# sttslife_2022-01-20.net
KiCad netlist of a schematic drawn in Altium Designer
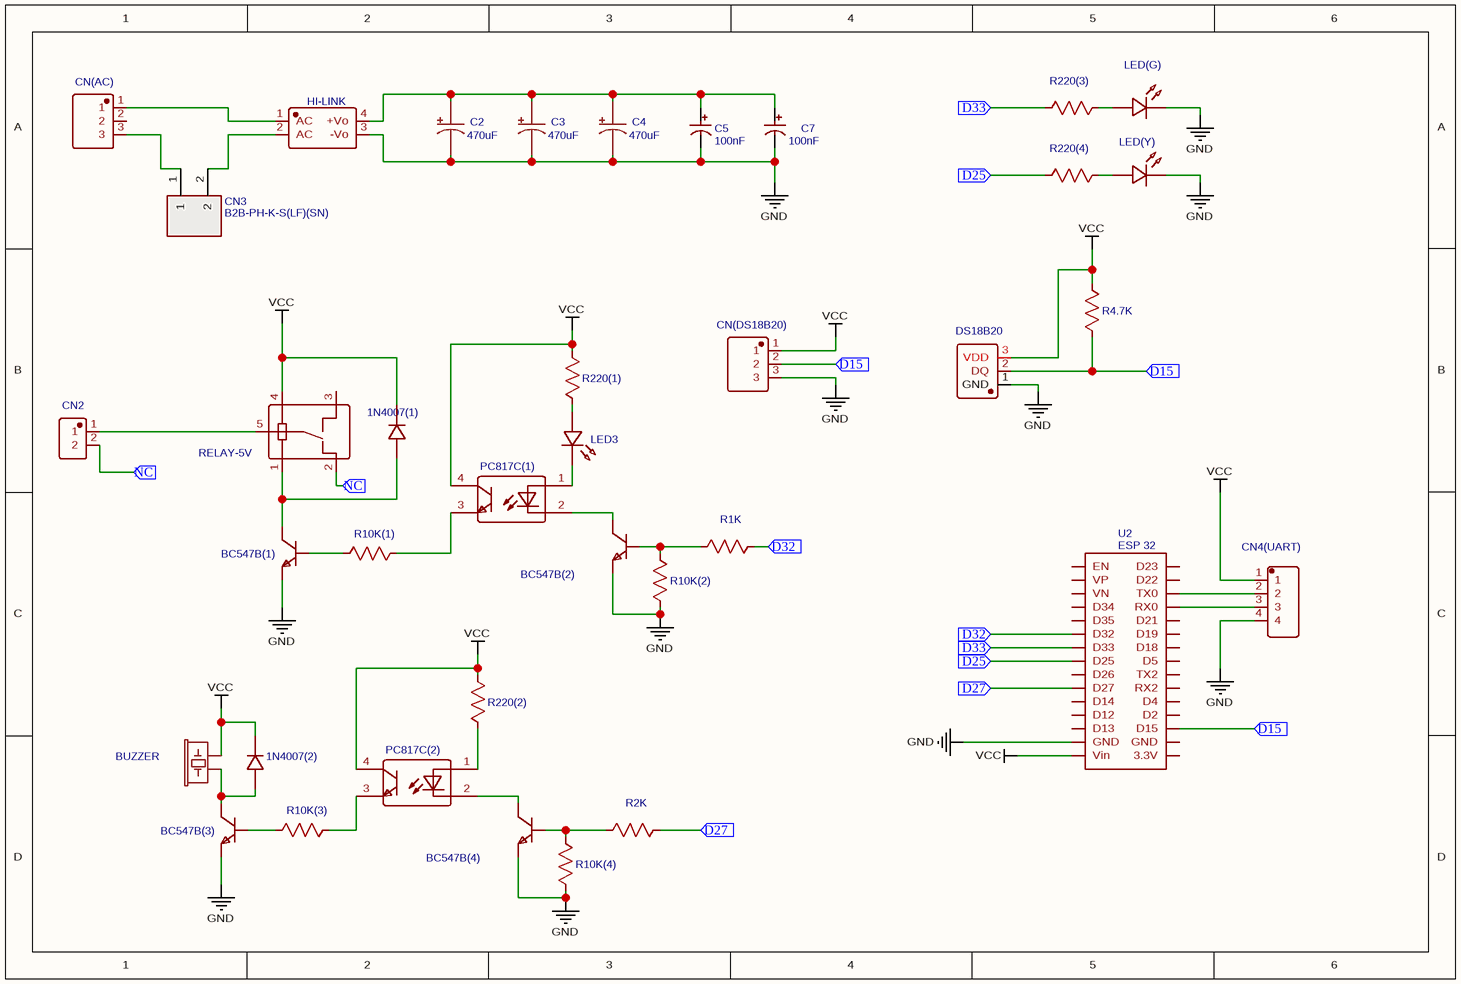
[diagram p0: sttslife_2022-01-20.schdoc]

(export (version "E")
  (design (tool "Eeschema 10.0.6"))
  (components
    (comp (ref "1N4007(1)")
      (value "1N4007")
      (fields (field (name "BOM_SUPPLIER PART") "C212822") (field (name "CONTRIBUTOR") "LCSC"))
      (libsource (lib "altium-import") (part "root_3_1N4007_"))
    )
    (comp (ref "1N4007(2)")
      (value "1N4007")
      (fields (field (name "BOM_SUPPLIER PART") "C212822") (field (name "CONTRIBUTOR") "LCSC"))
      (libsource (lib "altium-import") (part "root_3_1N4007_"))
    )
    (comp (ref "BC547B(1)")
      (value "BC547B")
      (fields (field (name "BOM_SUPPLIER PART") "C713613") (field (name "CONTRIBUTOR") "LCSC"))
      (libsource (lib "altium-import") (part "root_0_BC547B_"))
    )
    (comp (ref "BC547B(2)")
      (value "BC547B")
      (fields (field (name "BOM_SUPPLIER PART") "C713613") (field (name "CONTRIBUTOR") "LCSC"))
      (libsource (lib "altium-import") (part "root_0_BC547B_"))
    )
    (comp (ref "BC547B(3)")
      (value "BC547B")
      (fields (field (name "BOM_SUPPLIER PART") "C713613") (field (name "CONTRIBUTOR") "LCSC"))
      (libsource (lib "altium-import") (part "root_0_BC547B_"))
    )
    (comp (ref "BC547B(4)")
      (value "BC547B")
      (fields (field (name "BOM_SUPPLIER PART") "C713613") (field (name "CONTRIBUTOR") "LCSC"))
      (libsource (lib "altium-import") (part "root_0_BC547B_"))
    )
    (comp (ref "BUZZER")
      (value "BUZZER")
      (fields (field (name "CONTRIBUTOR") "SparkFun"))
      (libsource (lib "altium-import") (part "root_1_BUZZER_"))
    )
    (comp (ref "C2")
      (value "470uF")
      (fields
        (field (name "BOM_SUPPLIER PART") "C250976")
        (field (name "BOM_MANUFACTURER PART") "UKW1E471MPD")
        (field (name "CONTRIBUTOR") "LCSC")
      )
      (libsource (lib "altium-import") (part "root_0_470uF_"))
    )
    (comp (ref "C3")
      (value "470uF")
      (fields
        (field (name "BOM_SUPPLIER PART") "C250976")
        (field (name "BOM_MANUFACTURER PART") "UKW1E471MPD")
        (field (name "CONTRIBUTOR") "LCSC")
      )
      (libsource (lib "altium-import") (part "root_0_470uF_"))
    )
    (comp (ref "C4")
      (value "470uF")
      (fields
        (field (name "BOM_SUPPLIER PART") "C250976")
        (field (name "BOM_MANUFACTURER PART") "UKW1E471MPD")
        (field (name "CONTRIBUTOR") "LCSC")
      )
      (libsource (lib "altium-import") (part "root_0_470uF_"))
    )
    (comp (ref "C5")
      (value "100nF")
      (fields
        (field (name "BOM_MANUFACTURER PART") "0.1uF 50V 4*7")
        (field (name "BOM_SUPPLIER PART") "C45664")
      )
      (libsource (lib "altium-import") (part "root_0_100nF_"))
    )
    (comp (ref "C7")
      (value "100nF")
      (fields
        (field (name "BOM_MANUFACTURER PART") "0.1uF 50V 4*7")
        (field (name "BOM_SUPPLIER PART") "C45664")
      )
      (libsource (lib "altium-import") (part "root_0_100nF_"))
    )
    (comp (ref "CN(AC)")
      (value "A2501WR-3P")
      (fields (field (name "BOM_SUPPLIER PART") "C225400") (field (name "CONTRIBUTOR") "LCSC"))
      (libsource (lib "altium-import") (part "root_0_A2501WR-3P_"))
    )
    (comp (ref "CN(DS18B20)")
      (value "A2501WR-3P")
      (fields (field (name "BOM_SUPPLIER PART") "C225400") (field (name "CONTRIBUTOR") "LCSC"))
      (libsource (lib "altium-import") (part "root_0_A2501WR-3P_"))
    )
    (comp (ref "CN2")
      (value "X2581WR-02-N0SN")
      (fields (field (name "BOM_SUPPLIER PART") "C725750") (field (name "CONTRIBUTOR") "LCSC"))
      (libsource (lib "altium-import") (part "root_0_X2581WR-02-N0SN_"))
    )
    (comp (ref "CN3")
      (value "B2B-PH-K-S(LF)(SN)")
      (fields (field (name "BOM_SUPPLIER PART") "C131337") (field (name "CONTRIBUTOR") "LCSC"))
      (libsource (lib "altium-import") (part "root_1_B2B-PH-K-S(LF)(SN)_"))
    )
    (comp (ref "CN4(UART)")
      (value "PH-4AW")
      (fields (field (name "BOM_SUPPLIER PART") "C10401"))
      (libsource (lib "altium-import") (part "root_0_PH-4AW_"))
    )
    (comp (ref "DS18B20")
      (value "DS18B20")
      (fields (field (name "BOM_SUPPLIER PART") "C376006") (field (name "CONTRIBUTOR") "LCSC"))
      (libsource (lib "altium-import") (part "root_0_DS18B20_"))
    )
    (comp (ref "HI-LINK")
      (value "HI-LINK")
      (fields
        (field (name "BOM_SUPPLIER PART") "C465409")
        (field (name "BOM_MANUFACTURER PART") "HLK-20M24")
        (field (name "CONTRIBUTOR") "LCSC")
      )
      (libsource (lib "altium-import") (part "root_0_HI-LINK_"))
    )
    (comp (ref "LED(G)")
      (value "LED-TH-3mm_G")
      (fields
        (field (name "BOM_MANUFACTURER PART") "204-10SYGD/S530-E3")
        (field (name "BOM_SUPPLIER PART") "C85161")
        (field (name "CONTRIBUTOR") "LCEDA_Lib")
      )
      (libsource (lib "altium-import") (part "root_0_LED-TH-3mm_G_"))
    )
    (comp (ref "LED(Y)")
      (value "LED-TH-3mm_B")
      (fields
        (field (name "BOM_MANUFACTURER PART") "204-10SUBC/S400-A4")
        (field (name "BOM_SUPPLIER PART") "C86881")
        (field (name "CONTRIBUTOR") "LCEDA_Lib")
      )
      (libsource (lib "altium-import") (part "root_0_LED-TH-3mm_B_"))
    )
    (comp (ref "LED3")
      (value "LED-TH-3mm_R")
      (fields
        (field (name "BOM_MANUFACTURER PART") "204-10SDRD/S530-A3-L")
        (field (name "BOM_SUPPLIER PART") "C84774")
        (field (name "CONTRIBUTOR") "LCEDA_Lib")
      )
      (libsource (lib "altium-import") (part "root_3_LED-TH-3mm_R_"))
    )
    (comp (ref "PC817C(1)")
      (value "PC817C(1)")
      (fields
        (field (name "BOM_SUPPLIER PART") "C115500")
        (field (name "BOM_MANUFACTURER PART") "PC817C")
        (field (name "CONTRIBUTOR") "LCSC")
      )
      (libsource (lib "altium-import") (part "root_2_PC817C(1)_"))
    )
    (comp (ref "PC817C(2)")
      (value "PC817C(1)")
      (fields
        (field (name "BOM_SUPPLIER PART") "C115500")
        (field (name "BOM_MANUFACTURER PART") "PC817C")
        (field (name "CONTRIBUTOR") "LCSC")
      )
      (libsource (lib "altium-import") (part "root_2_PC817C(1)_"))
    )
    (comp (ref "R1K")
      (value "1k")
      (fields (field (name "CONTRIBUTOR") "LCEDA_Lib"))
      (libsource (lib "altium-import") (part "root_0_1k_"))
    )
    (comp (ref "R2K")
      (value "1k")
      (fields (field (name "CONTRIBUTOR") "LCEDA_Lib"))
      (libsource (lib "altium-import") (part "root_0_1k_"))
    )
    (comp (ref "R4.7K")
      (value "1k")
      (fields (field (name "CONTRIBUTOR") "LCEDA_Lib"))
      (libsource (lib "altium-import") (part "root_1_1k_"))
    )
    (comp (ref "R10K(1)")
      (value "1k")
      (fields (field (name "CONTRIBUTOR") "LCEDA_Lib"))
      (libsource (lib "altium-import") (part "root_0_1k_"))
    )
    (comp (ref "R10K(2)")
      (value "1k")
      (fields (field (name "CONTRIBUTOR") "LCEDA_Lib"))
      (libsource (lib "altium-import") (part "root_3_1k_"))
    )
    (comp (ref "R10K(3)")
      (value "1k")
      (fields (field (name "CONTRIBUTOR") "LCEDA_Lib"))
      (libsource (lib "altium-import") (part "root_0_1k_"))
    )
    (comp (ref "R10K(4)")
      (value "1k")
      (fields (field (name "CONTRIBUTOR") "LCEDA_Lib"))
      (libsource (lib "altium-import") (part "root_3_1k_"))
    )
    (comp (ref "R220(1)")
      (value "1k")
      (fields (field (name "CONTRIBUTOR") "LCEDA_Lib"))
      (libsource (lib "altium-import") (part "root_3_1k_"))
    )
    (comp (ref "R220(2)")
      (value "1k")
      (fields (field (name "CONTRIBUTOR") "LCEDA_Lib"))
      (libsource (lib "altium-import") (part "root_3_1k_"))
    )
    (comp (ref "R220(3)")
      (value "1k")
      (fields (field (name "CONTRIBUTOR") "LCEDA_Lib"))
      (libsource (lib "altium-import") (part "root_2_1k_"))
    )
    (comp (ref "R220(4)")
      (value "1k")
      (fields (field (name "CONTRIBUTOR") "LCEDA_Lib"))
      (libsource (lib "altium-import") (part "root_2_1k_"))
    )
    (comp (ref "RELAY-5V")
      (value "SRD-S-105D")
      (fields (field (name "BOM_SUPPLIER PART") "C276432") (field (name "CONTRIBUTOR") "LCSC"))
      (libsource (lib "altium-import") (part "root_0_SRD-S-105D_"))
    )
    (comp (ref "U2")
      (value "ESP 32")
      (fields (field (name "CONTRIBUTOR") "parinya1051"))
      (libsource (lib "altium-import") (part "root_0_ESP 32_"))
    )
  )
  (nets
    (net (code "1") (name "/D15") (class "Default")
      (node (ref "CN(DS18B20)") (pin "2") (pinfunction "2_2") (pintype "passive"))
      (node (ref "DS18B20") (pin "2") (pinfunction "DQ_2") (pintype "passive"))
      (node (ref "R4.7K") (pin "1") (pinfunction "1_1") (pintype "passive"))
      (node (ref "U2") (pin "18") (pinfunction "D15_18") (pintype "passive"))
    )
    (net (code "2") (name "/D25") (class "Default")
      (node (ref "R220(4)") (pin "2") (pinfunction "2_2") (pintype "passive"))
      (node (ref "U2") (pin "8") (pinfunction "D25_8") (pintype "passive"))
    )
    (net (code "3") (name "/D27") (class "Default")
      (node (ref "R2K") (pin "2") (pinfunction "2_2") (pintype "passive"))
      (node (ref "U2") (pin "10") (pinfunction "D27_10") (pintype "passive"))
    )
    (net (code "4") (name "/D32") (class "Default")
      (node (ref "R1K") (pin "2") (pinfunction "2_2") (pintype "passive"))
      (node (ref "U2") (pin "6") (pinfunction "D32_6") (pintype "passive"))
    )
    (net (code "5") (name "/D33") (class "Default")
      (node (ref "R220(3)") (pin "2") (pinfunction "2_2") (pintype "passive"))
      (node (ref "U2") (pin "7") (pinfunction "D33_7") (pintype "passive"))
    )
    (net (code "6") (name "/NC") (class "Default")
      (node (ref "CN2") (pin "2") (pinfunction "2_2") (pintype "passive"))
      (node (ref "RELAY-5V") (pin "2") (pinfunction "2_2") (pintype "passive"))
    )
    (net (code "7") (name "GND") (class "Default")
      (node (ref "BC547B(1)") (pin "3") (pinfunction "E_3") (pintype "passive"))
      (node (ref "BC547B(2)") (pin "3") (pinfunction "E_3") (pintype "passive"))
      (node (ref "BC547B(3)") (pin "3") (pinfunction "E_3") (pintype "passive"))
      (node (ref "BC547B(4)") (pin "3") (pinfunction "E_3") (pintype "passive"))
      (node (ref "C2") (pin "2") (pinfunction "2_2") (pintype "passive"))
      (node (ref "C3") (pin "2") (pinfunction "2_2") (pintype "passive"))
      (node (ref "C4") (pin "2") (pinfunction "2_2") (pintype "passive"))
      (node (ref "C5") (pin "2") (pinfunction "2_2") (pintype "passive"))
      (node (ref "C7") (pin "2") (pinfunction "2_2") (pintype "passive"))
      (node (ref "CN(DS18B20)") (pin "3") (pinfunction "3_3") (pintype "passive"))
      (node (ref "CN4(UART)") (pin "4") (pinfunction "4_4") (pintype "passive"))
      (node (ref "DS18B20") (pin "1") (pinfunction "GND_1") (pintype "passive"))
      (node (ref "HI-LINK") (pin "3") (pinfunction "-Vo_3") (pintype "passive"))
      (node (ref "LED(G)") (pin "2") (pinfunction "2_2") (pintype "passive"))
      (node (ref "LED(Y)") (pin "2") (pinfunction "2_2") (pintype "passive"))
      (node (ref "R10K(2)") (pin "2") (pinfunction "2_2") (pintype "passive"))
      (node (ref "R10K(4)") (pin "2") (pinfunction "2_2") (pintype "passive"))
      (node (ref "U2") (pin "14") (pinfunction "GND_14") (pintype "passive"))
    )
    (net (code "8") (name "Net-(BC547B(1)-B)") (class "Default")
      (node (ref "BC547B(1)") (pin "2") (pinfunction "B_2") (pintype "passive"))
      (node (ref "R10K(1)") (pin "1") (pinfunction "1_1") (pintype "passive"))
    )
    (net (code "9") (name "Net-(BC547B(1)-C)") (class "Default")
      (node (ref "1N4007(1)") (pin "2") (pinfunction "2_2") (pintype "passive"))
      (node (ref "BC547B(1)") (pin "1") (pinfunction "C_1") (pintype "passive"))
      (node (ref "RELAY-5V") (pin "1") (pinfunction "1_1") (pintype "passive"))
    )
    (net (code "10") (name "Net-(BC547B(2)-B)") (class "Default")
      (node (ref "BC547B(2)") (pin "2") (pinfunction "B_2") (pintype "passive"))
      (node (ref "R10K(2)") (pin "1") (pinfunction "1_1") (pintype "passive"))
      (node (ref "R1K") (pin "1") (pinfunction "1_1") (pintype "passive"))
    )
    (net (code "11") (name "Net-(BC547B(2)-C)") (class "Default")
      (node (ref "BC547B(2)") (pin "1") (pinfunction "C_1") (pintype "passive"))
      (node (ref "PC817C(1)") (pin "2") (pinfunction "CAT_2") (pintype "passive"))
    )
    (net (code "12") (name "Net-(BC547B(3)-B)") (class "Default")
      (node (ref "BC547B(3)") (pin "2") (pinfunction "B_2") (pintype "passive"))
      (node (ref "R10K(3)") (pin "1") (pinfunction "1_1") (pintype "passive"))
    )
    (net (code "13") (name "Net-(BC547B(3)-C)") (class "Default")
      (node (ref "1N4007(2)") (pin "2") (pinfunction "2_2") (pintype "passive"))
      (node (ref "BC547B(3)") (pin "1") (pinfunction "C_1") (pintype "passive"))
      (node (ref "BUZZER") (pin "+") (pinfunction "1_+") (pintype "passive"))
    )
    (net (code "14") (name "Net-(BC547B(4)-B)") (class "Default")
      (node (ref "BC547B(4)") (pin "2") (pinfunction "B_2") (pintype "passive"))
      (node (ref "R10K(4)") (pin "1") (pinfunction "1_1") (pintype "passive"))
      (node (ref "R2K") (pin "1") (pinfunction "1_1") (pintype "passive"))
    )
    (net (code "15") (name "Net-(BC547B(4)-C)") (class "Default")
      (node (ref "BC547B(4)") (pin "1") (pinfunction "C_1") (pintype "passive"))
      (node (ref "PC817C(2)") (pin "2") (pinfunction "CAT_2") (pintype "passive"))
    )
    (net (code "16") (name "Net-(CN(AC)-Pad1)") (class "Default")
      (node (ref "CN(AC)") (pin "1") (pinfunction "1_1") (pintype "passive"))
      (node (ref "HI-LINK") (pin "1") (pinfunction "AC_1") (pintype "passive"))
    )
    (net (code "17") (name "Net-(CN(AC)-Pad3)") (class "Default")
      (node (ref "CN(AC)") (pin "3") (pinfunction "3_3") (pintype "passive"))
      (node (ref "CN3") (pin "1") (pinfunction "1_1") (pintype "passive"))
    )
    (net (code "18") (name "Net-(CN2-Pad1)") (class "Default")
      (node (ref "CN2") (pin "1") (pinfunction "1_1") (pintype "passive"))
      (node (ref "RELAY-5V") (pin "5") (pinfunction "5_5") (pintype "passive"))
    )
    (net (code "19") (name "Net-(CN3-Pad2)") (class "Default")
      (node (ref "CN3") (pin "2") (pinfunction "2_2") (pintype "passive"))
      (node (ref "HI-LINK") (pin "2") (pinfunction "AC_2") (pintype "passive"))
    )
    (net (code "20") (name "Net-(HI-LINK-+Vo)") (class "Default")
      (node (ref "C2") (pin "1") (pinfunction "1_1") (pintype "passive"))
      (node (ref "C3") (pin "1") (pinfunction "1_1") (pintype "passive"))
      (node (ref "C4") (pin "1") (pinfunction "1_1") (pintype "passive"))
      (node (ref "C5") (pin "1") (pinfunction "1_1") (pintype "passive"))
      (node (ref "C7") (pin "1") (pinfunction "1_1") (pintype "passive"))
      (node (ref "HI-LINK") (pin "4") (pinfunction "+Vo_4") (pintype "passive"))
    )
    (net (code "21") (name "Net-(LED(G)-Pad1)") (class "Default")
      (node (ref "LED(G)") (pin "1") (pinfunction "1_1") (pintype "passive"))
      (node (ref "R220(3)") (pin "1") (pinfunction "1_1") (pintype "passive"))
    )
    (net (code "22") (name "Net-(LED(Y)-Pad1)") (class "Default")
      (node (ref "LED(Y)") (pin "1") (pinfunction "1_1") (pintype "passive"))
      (node (ref "R220(4)") (pin "1") (pinfunction "1_1") (pintype "passive"))
    )
    (net (code "23") (name "Net-(LED3-Pad1)") (class "Default")
      (node (ref "LED3") (pin "1") (pinfunction "1_1") (pintype "passive"))
      (node (ref "R220(1)") (pin "2") (pinfunction "2_2") (pintype "passive"))
    )
    (net (code "24") (name "Net-(PC817C(1)-AN)") (class "Default")
      (node (ref "LED3") (pin "2") (pinfunction "2_2") (pintype "passive"))
      (node (ref "PC817C(1)") (pin "1") (pinfunction "AN_1") (pintype "passive"))
    )
    (net (code "25") (name "Net-(PC817C(1)-EM)") (class "Default")
      (node (ref "PC817C(1)") (pin "3") (pinfunction "EM_3") (pintype "passive"))
      (node (ref "R10K(1)") (pin "2") (pinfunction "2_2") (pintype "passive"))
    )
    (net (code "26") (name "Net-(PC817C(2)-AN)") (class "Default")
      (node (ref "PC817C(2)") (pin "1") (pinfunction "AN_1") (pintype "passive"))
      (node (ref "R220(2)") (pin "2") (pinfunction "2_2") (pintype "passive"))
    )
    (net (code "27") (name "Net-(PC817C(2)-EM)") (class "Default")
      (node (ref "PC817C(2)") (pin "3") (pinfunction "EM_3") (pintype "passive"))
      (node (ref "R10K(3)") (pin "2") (pinfunction "2_2") (pintype "passive"))
    )
    (net (code "28") (name "Net-(U2-RX0)") (class "Default")
      (node (ref "CN4(UART)") (pin "3") (pinfunction "3_3") (pintype "passive"))
      (node (ref "U2") (pin "27") (pinfunction "RX0_27") (pintype "passive"))
    )
    (net (code "29") (name "Net-(U2-TX0)") (class "Default")
      (node (ref "CN4(UART)") (pin "2") (pinfunction "2_2") (pintype "passive"))
      (node (ref "U2") (pin "28") (pinfunction "TX0_28") (pintype "passive"))
    )
    (net (code "30") (name "VCC") (class "Default")
      (node (ref "1N4007(1)") (pin "1") (pinfunction "1_1") (pintype "passive"))
      (node (ref "1N4007(2)") (pin "1") (pinfunction "1_1") (pintype "passive"))
      (node (ref "BUZZER") (pin "-") (pinfunction "2_-") (pintype "passive"))
      (node (ref "CN(DS18B20)") (pin "1") (pinfunction "1_1") (pintype "passive"))
      (node (ref "CN4(UART)") (pin "1") (pinfunction "1_1") (pintype "passive"))
      (node (ref "DS18B20") (pin "3") (pinfunction "VDD_3") (pintype "passive"))
      (node (ref "PC817C(1)") (pin "4") (pinfunction "COL_4") (pintype "passive"))
      (node (ref "PC817C(2)") (pin "4") (pinfunction "COL_4") (pintype "passive"))
      (node (ref "R220(1)") (pin "1") (pinfunction "1_1") (pintype "passive"))
      (node (ref "R220(2)") (pin "1") (pinfunction "1_1") (pintype "passive"))
      (node (ref "R4.7K") (pin "2") (pinfunction "2_2") (pintype "passive"))
      (node (ref "RELAY-5V") (pin "4") (pinfunction "4_4") (pintype "passive"))
      (node (ref "U2") (pin "15") (pinfunction "Vin_15") (pintype "passive"))
    )
    (net (code "31") (name "unconnected-(CN(AC)-Pad2)") (class "Default")
      (node (ref "CN(AC)") (pin "2") (pinfunction "2_2") (pintype "passive"))
    )
    (net (code "32") (name "unconnected-(RELAY-5V-Pad3)") (class "Default")
      (node (ref "RELAY-5V") (pin "3") (pinfunction "3_3") (pintype "passive"))
    )
    (net (code "33") (name "unconnected-(U2-3.3V-Pad16)") (class "Default")
      (node (ref "U2") (pin "16") (pinfunction "3.3V_16") (pintype "passive"))
    )
    (net (code "34") (name "unconnected-(U2-D2-Pad19)") (class "Default")
      (node (ref "U2") (pin "19") (pinfunction "D2_19") (pintype "passive"))
    )
    (net (code "35") (name "unconnected-(U2-D4-Pad20)") (class "Default")
      (node (ref "U2") (pin "20") (pinfunction "D4_20") (pintype "passive"))
    )
    (net (code "36") (name "unconnected-(U2-D5-Pad23)") (class "Default")
      (node (ref "U2") (pin "23") (pinfunction "D5_23") (pintype "passive"))
    )
    (net (code "37") (name "unconnected-(U2-D12-Pad12)") (class "Default")
      (node (ref "U2") (pin "12") (pinfunction "D12_12") (pintype "passive"))
    )
    (net (code "38") (name "unconnected-(U2-D13-Pad13)") (class "Default")
      (node (ref "U2") (pin "13") (pinfunction "D13_13") (pintype "passive"))
    )
    (net (code "39") (name "unconnected-(U2-D14-Pad11)") (class "Default")
      (node (ref "U2") (pin "11") (pinfunction "D14_11") (pintype "passive"))
    )
    (net (code "40") (name "unconnected-(U2-D18-Pad24)") (class "Default")
      (node (ref "U2") (pin "24") (pinfunction "D18_24") (pintype "passive"))
    )
    (net (code "41") (name "unconnected-(U2-D19-Pad25)") (class "Default")
      (node (ref "U2") (pin "25") (pinfunction "D19_25") (pintype "passive"))
    )
    (net (code "42") (name "unconnected-(U2-D21-Pad26)") (class "Default")
      (node (ref "U2") (pin "26") (pinfunction "D21_26") (pintype "passive"))
    )
    (net (code "43") (name "unconnected-(U2-D22-Pad29)") (class "Default")
      (node (ref "U2") (pin "29") (pinfunction "D22_29") (pintype "passive"))
    )
    (net (code "44") (name "unconnected-(U2-D23-Pad30)") (class "Default")
      (node (ref "U2") (pin "30") (pinfunction "D23_30") (pintype "passive"))
    )
    (net (code "45") (name "unconnected-(U2-D26-Pad9)") (class "Default")
      (node (ref "U2") (pin "9") (pinfunction "D26_9") (pintype "passive"))
    )
    (net (code "46") (name "unconnected-(U2-D34-Pad4)") (class "Default")
      (node (ref "U2") (pin "4") (pinfunction "D34_4") (pintype "passive"))
    )
    (net (code "47") (name "unconnected-(U2-D35-Pad5)") (class "Default")
      (node (ref "U2") (pin "5") (pinfunction "D35_5") (pintype "passive"))
    )
    (net (code "48") (name "unconnected-(U2-EN-Pad1)") (class "Default")
      (node (ref "U2") (pin "1") (pinfunction "EN_1") (pintype "passive"))
    )
    (net (code "49") (name "unconnected-(U2-GND-Pad17)") (class "Default")
      (node (ref "U2") (pin "17") (pinfunction "GND_17") (pintype "passive"))
    )
    (net (code "50") (name "unconnected-(U2-RX2-Pad21)") (class "Default")
      (node (ref "U2") (pin "21") (pinfunction "RX2_21") (pintype "passive"))
    )
    (net (code "51") (name "unconnected-(U2-TX2-Pad22)") (class "Default")
      (node (ref "U2") (pin "22") (pinfunction "TX2_22") (pintype "passive"))
    )
    (net (code "52") (name "unconnected-(U2-VN-Pad3)") (class "Default")
      (node (ref "U2") (pin "3") (pinfunction "VN_3") (pintype "passive"))
    )
    (net (code "53") (name "unconnected-(U2-VP-Pad2)") (class "Default")
      (node (ref "U2") (pin "2") (pinfunction "VP_2") (pintype "passive"))
    )
  )
)
